# APA102.net
KiCad netlist of a schematic drawn in Altium Designer
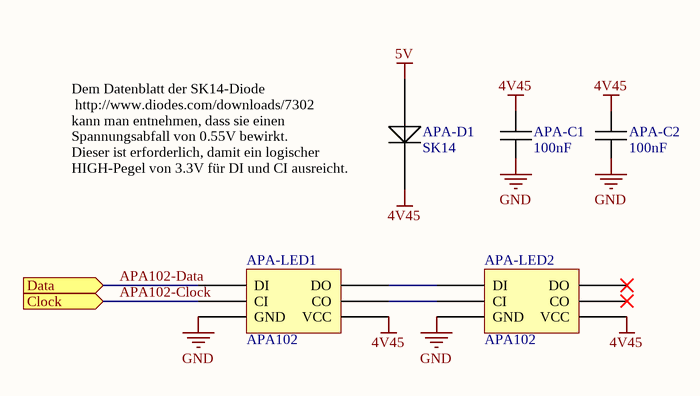
[diagram p0: APA102.SchDoc]

(export (version "E")
  (design (tool "Eeschema 10.0.6"))
  (components
    (comp (ref "APA-C1")
      (value "100nF")
      (footprint "C 0805 wide")
      (libsource (lib "Standard") (part "Capacitor"))
    )
    (comp (ref "APA-C2")
      (value "100nF")
      (footprint "C 0805 wide")
      (libsource (lib "Standard") (part "Capacitor"))
    )
    (comp (ref "APA-D1") (value "SK14") (footprint "SC-90") (libsource (lib "Standard") (part "Diode")))
    (comp (ref "APA-LED1")
      (value "APA102")
      (footprint "LED SMD 5x5mm")
      (libsource (lib "LEDs") (part "APA102"))
    )
    (comp (ref "APA-LED2")
      (value "APA102")
      (footprint "LED SMD 5x5mm")
      (libsource (lib "LEDs") (part "APA102"))
    )
  )
  (nets
    (net (code "1") (name "/APA102-Clock") (class "Default")
      (node (ref "APA-LED1") (pin "2") (pinfunction "CI_2") (pintype "passive"))
    )
    (net (code "2") (name "/APA102-Data") (class "Default")
      (node (ref "APA-LED1") (pin "1") (pinfunction "DI_1") (pintype "passive"))
    )
    (net (code "3") (name "4V45") (class "Default")
      (node (ref "APA-C1") (pin "1") (pinfunction "1_1") (pintype "passive"))
      (node (ref "APA-C2") (pin "1") (pinfunction "1_1") (pintype "passive"))
      (node (ref "APA-D1") (pin "1") (pinfunction "1_1") (pintype "passive"))
      (node (ref "APA-LED1") (pin "4") (pinfunction "VCC_4") (pintype "passive"))
      (node (ref "APA-LED2") (pin "4") (pinfunction "VCC_4") (pintype "passive"))
    )
    (net (code "4") (name "5V") (class "Default")
      (node (ref "APA-D1") (pin "2") (pinfunction "2_2") (pintype "passive"))
    )
    (net (code "5") (name "GND") (class "Default")
      (node (ref "APA-C1") (pin "2") (pinfunction "1_2") (pintype "passive"))
      (node (ref "APA-C2") (pin "2") (pinfunction "1_2") (pintype "passive"))
      (node (ref "APA-LED1") (pin "3") (pinfunction "GND_3") (pintype "passive"))
      (node (ref "APA-LED2") (pin "3") (pinfunction "GND_3") (pintype "passive"))
    )
    (net (code "6") (name "Net-(APA-LED1-CO)") (class "Default")
      (node (ref "APA-LED1") (pin "5") (pinfunction "CO_5") (pintype "passive"))
      (node (ref "APA-LED2") (pin "2") (pinfunction "CI_2") (pintype "passive"))
    )
    (net (code "7") (name "Net-(APA-LED1-DO)") (class "Default")
      (node (ref "APA-LED1") (pin "6") (pinfunction "DO_6") (pintype "passive"))
      (node (ref "APA-LED2") (pin "1") (pinfunction "DI_1") (pintype "passive"))
    )
    (net (code "8") (name "unconnected-(APA-LED2-CO-Pad5)") (class "Default")
      (node (ref "APA-LED2") (pin "5") (pinfunction "CO_5") (pintype "passive+no_connect"))
    )
    (net (code "9") (name "unconnected-(APA-LED2-DO-Pad6)") (class "Default")
      (node (ref "APA-LED2") (pin "6") (pinfunction "DO_6") (pintype "passive+no_connect"))
    )
  )
)
